# motiondetector.net
KiCad netlist of a schematic drawn in EAGLE
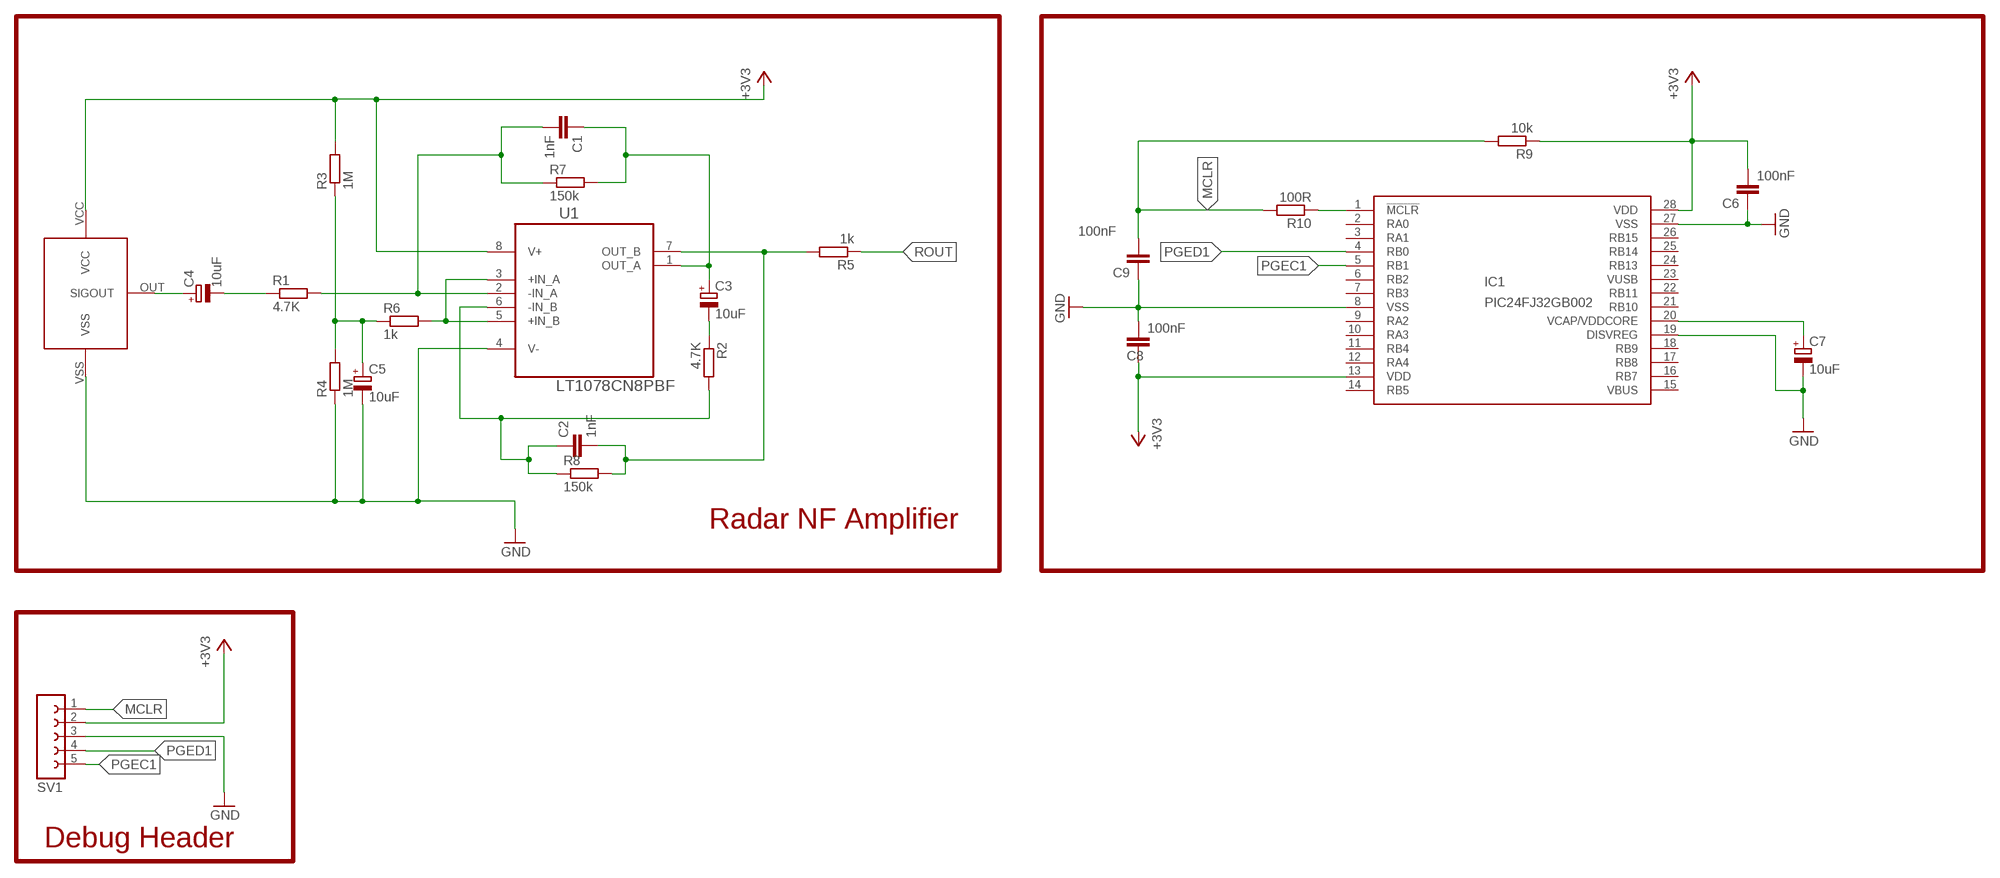
[diagram p0: schematic, sheet 1]

(export (version "E")
  (design (tool "Eeschema 10.0.6"))
  (components
    (comp (ref "C1")
      (value "1nF")
      (footprint "eagle-import:C025-025X050")
      (libsource (lib "eagle-import") (part "C-EU025-025X050"))
    )
    (comp (ref "C2")
      (value "1nF")
      (footprint "eagle-import:C025-025X050")
      (libsource (lib "eagle-import") (part "C-EU025-025X050"))
    )
    (comp (ref "C3")
      (value "10uF")
      (footprint "eagle-import:E2,5-5")
      (libsource (lib "eagle-import") (part "CPOL-EUE2.5-5"))
    )
    (comp (ref "C4")
      (value "10uF")
      (footprint "eagle-import:E2,5-5")
      (libsource (lib "eagle-import") (part "CPOL-EUE2.5-5"))
    )
    (comp (ref "C5")
      (value "10uF")
      (footprint "eagle-import:E2,5-5")
      (libsource (lib "eagle-import") (part "CPOL-EUE2.5-5"))
    )
    (comp (ref "C6")
      (value "100nF")
      (footprint "eagle-import:C025-025X050")
      (libsource (lib "eagle-import") (part "C-EU025-025X050"))
    )
    (comp (ref "C7")
      (value "10uF")
      (footprint "eagle-import:E2,5-5")
      (libsource (lib "eagle-import") (part "CPOL-EUE2.5-5"))
    )
    (comp (ref "C8")
      (value "100nF")
      (footprint "eagle-import:C025-025X050")
      (libsource (lib "eagle-import") (part "C-EU025-025X050"))
    )
    (comp (ref "C9")
      (value "100nF")
      (footprint "eagle-import:C025-025X050")
      (libsource (lib "eagle-import") (part "C-EU025-025X050"))
    )
    (comp (ref "IC1")
      (value "PIC24FJ32GB002")
      (footprint "eagle-import:DIL28-3")
      (libsource (lib "eagle-import") (part "PIC24FJ32GB002"))
    )
    (comp (ref "R1")
      (value "4.7K")
      (footprint "eagle-import:0207_10")
      (libsource (lib "eagle-import") (part "R-EU_0207/10"))
    )
    (comp (ref "R2")
      (value "4.7K")
      (footprint "eagle-import:0207_10")
      (libsource (lib "eagle-import") (part "R-EU_0207/10"))
    )
    (comp (ref "R3")
      (value "1M")
      (footprint "eagle-import:0207_10")
      (libsource (lib "eagle-import") (part "R-EU_0207/10"))
    )
    (comp (ref "R4")
      (value "1M")
      (footprint "eagle-import:0207_10")
      (libsource (lib "eagle-import") (part "R-EU_0207/10"))
    )
    (comp (ref "R5")
      (value "1k")
      (footprint "eagle-import:0207_10")
      (libsource (lib "eagle-import") (part "R-EU_0207/10"))
    )
    (comp (ref "R6")
      (value "1k")
      (footprint "eagle-import:0207_10")
      (libsource (lib "eagle-import") (part "R-EU_0207/10"))
    )
    (comp (ref "R7")
      (value "150k")
      (footprint "eagle-import:0207_10")
      (libsource (lib "eagle-import") (part "R-EU_0207/10"))
    )
    (comp (ref "R8")
      (value "150k")
      (footprint "eagle-import:0207_10")
      (libsource (lib "eagle-import") (part "R-EU_0207/10"))
    )
    (comp (ref "R9")
      (value "10k")
      (footprint "eagle-import:0207_10")
      (libsource (lib "eagle-import") (part "R-EU_0207/10"))
    )
    (comp (ref "R10")
      (value "100R")
      (footprint "eagle-import:0207_10")
      (libsource (lib "eagle-import") (part "R-EU_0207/10"))
    )
    (comp (ref "SV1")
      (value "FE05-1")
      (footprint "eagle-import:FE05-1")
      (libsource (lib "eagle-import") (part "FE05-1"))
    )
    (comp (ref "U$1")
      (value "RSM3650")
      (footprint "eagle-import:RSM3650")
      (libsource (lib "eagle-import") (part "RSM3650"))
    )
    (comp (ref "U1")
      (value "LT1078CN8PBF")
      (footprint "eagle-import:DIP254P762X393-8")
      (fields (field (name "MPN") "LT1078CN8#PBF"))
      (libsource (lib "eagle-import") (part "LT1078CN8PBF"))
    )
  )
  (nets
    (net (code "1") (name "+3V3") (class "Default")
      (node (ref "C6") (pin "2") (pinfunction "2_2") (pintype "passive"))
      (node (ref "C8") (pin "1") (pinfunction "1_1") (pintype "passive"))
      (node (ref "IC1") (pin "13") (pinfunction "VDD_13") (pintype "power_in"))
      (node (ref "IC1") (pin "28") (pinfunction "VDD_28") (pintype "power_in"))
      (node (ref "R3") (pin "2") (pinfunction "2_2") (pintype "passive"))
      (node (ref "R9") (pin "1") (pinfunction "1_1") (pintype "passive"))
      (node (ref "SV1") (pin "2") (pinfunction "2_2") (pintype "passive"))
      (node (ref "U$1") (pin "VCC") (pinfunction "VCC_VCC") (pintype "power_in"))
      (node (ref "U1") (pin "8") (pinfunction "V+_8") (pintype "power_in"))
    )
    (net (code "2") (name "GND") (class "Default")
      (node (ref "C5") (pin "-") (pinfunction "-_-") (pintype "passive"))
      (node (ref "C6") (pin "1") (pinfunction "1_1") (pintype "passive"))
      (node (ref "C7") (pin "-") (pinfunction "-_-") (pintype "passive"))
      (node (ref "C8") (pin "2") (pinfunction "2_2") (pintype "passive"))
      (node (ref "C9") (pin "1") (pinfunction "1_1") (pintype "passive"))
      (node (ref "IC1") (pin "19") (pinfunction "DISVREG_19") (pintype "passive"))
      (node (ref "IC1") (pin "27") (pinfunction "VSS_27") (pintype "power_in"))
      (node (ref "IC1") (pin "8") (pinfunction "VSS_8") (pintype "power_in"))
      (node (ref "R4") (pin "1") (pinfunction "1_1") (pintype "passive"))
      (node (ref "SV1") (pin "3") (pinfunction "3_3") (pintype "passive"))
      (node (ref "U$1") (pin "VSS") (pinfunction "VSS_VSS") (pintype "power_in"))
      (node (ref "U1") (pin "4") (pinfunction "V-_4") (pintype "power_in"))
    )
    (net (code "3") (name "MCLR") (class "Default")
      (node (ref "C9") (pin "2") (pinfunction "2_2") (pintype "passive"))
      (node (ref "R10") (pin "2") (pinfunction "2_2") (pintype "passive"))
      (node (ref "R9") (pin "2") (pinfunction "2_2") (pintype "passive"))
      (node (ref "SV1") (pin "1") (pinfunction "1_1") (pintype "passive"))
    )
    (net (code "4") (name "Net-(C3-Pad-)") (class "Default")
      (node (ref "C3") (pin "-") (pinfunction "-_-") (pintype "passive"))
      (node (ref "R2") (pin "1") (pinfunction "1_1") (pintype "passive"))
    )
    (net (code "5") (name "Net-(C4-Pad-)") (class "Default")
      (node (ref "C4") (pin "-") (pinfunction "-_-") (pintype "passive"))
      (node (ref "R1") (pin "1") (pinfunction "1_1") (pintype "passive"))
    )
    (net (code "6") (name "Net-(C5-Pad+)") (class "Default")
      (node (ref "C5") (pin "+") (pinfunction "+_+") (pintype "passive"))
      (node (ref "R3") (pin "1") (pinfunction "1_1") (pintype "passive"))
      (node (ref "R4") (pin "2") (pinfunction "2_2") (pintype "passive"))
      (node (ref "R6") (pin "1") (pinfunction "1_1") (pintype "passive"))
    )
    (net (code "7") (name "Net-(IC1-VCAP{slash}VDDCORE)") (class "Default")
      (node (ref "C7") (pin "+") (pinfunction "+_+") (pintype "passive"))
      (node (ref "IC1") (pin "20") (pinfunction "VCAP/VDDCORE_20") (pintype "power_in"))
    )
    (net (code "8") (name "Net-(IC1-~{MCLR})") (class "Default")
      (node (ref "IC1") (pin "1") (pinfunction "~{MCLR}_1") (pintype "bidirectional"))
      (node (ref "R10") (pin "1") (pinfunction "1_1") (pintype "passive"))
    )
    (net (code "9") (name "Net-(U$1-SIGOUT)") (class "Default")
      (node (ref "C4") (pin "+") (pinfunction "+_+") (pintype "passive"))
      (node (ref "U$1") (pin "OUT") (pinfunction "SIGOUT_OUT") (pintype "output"))
    )
    (net (code "10") (name "Net-(U1-+IN_A)") (class "Default")
      (node (ref "R6") (pin "2") (pinfunction "2_2") (pintype "passive"))
      (node (ref "U1") (pin "3") (pinfunction "+IN_A_3") (pintype "input"))
      (node (ref "U1") (pin "5") (pinfunction "+IN_B_5") (pintype "input"))
    )
    (net (code "11") (name "Net-(U1--IN_A)") (class "Default")
      (node (ref "C1") (pin "2") (pinfunction "2_2") (pintype "passive"))
      (node (ref "R1") (pin "2") (pinfunction "2_2") (pintype "passive"))
      (node (ref "R7") (pin "1") (pinfunction "1_1") (pintype "passive"))
      (node (ref "U1") (pin "2") (pinfunction "-IN_A_2") (pintype "input"))
    )
    (net (code "12") (name "Net-(U1--IN_B)") (class "Default")
      (node (ref "C2") (pin "1") (pinfunction "1_1") (pintype "passive"))
      (node (ref "R2") (pin "2") (pinfunction "2_2") (pintype "passive"))
      (node (ref "R8") (pin "1") (pinfunction "1_1") (pintype "passive"))
      (node (ref "U1") (pin "6") (pinfunction "-IN_B_6") (pintype "input"))
    )
    (net (code "13") (name "Net-(U1-OUT_A)") (class "Default")
      (node (ref "C1") (pin "1") (pinfunction "1_1") (pintype "passive"))
      (node (ref "C3") (pin "+") (pinfunction "+_+") (pintype "passive"))
      (node (ref "R7") (pin "2") (pinfunction "2_2") (pintype "passive"))
      (node (ref "U1") (pin "1") (pinfunction "OUT_A_1") (pintype "output"))
    )
    (net (code "14") (name "Net-(U1-OUT_B)") (class "Default")
      (node (ref "C2") (pin "2") (pinfunction "2_2") (pintype "passive"))
      (node (ref "R5") (pin "2") (pinfunction "2_2") (pintype "passive"))
      (node (ref "R8") (pin "2") (pinfunction "2_2") (pintype "passive"))
      (node (ref "U1") (pin "7") (pinfunction "OUT_B_7") (pintype "output"))
    )
    (net (code "15") (name "PGEC1") (class "Default")
      (node (ref "IC1") (pin "5") (pinfunction "RB1_5") (pintype "bidirectional"))
      (node (ref "SV1") (pin "5") (pinfunction "5_5") (pintype "passive"))
    )
    (net (code "16") (name "PGED1") (class "Default")
      (node (ref "IC1") (pin "4") (pinfunction "RB0_4") (pintype "bidirectional"))
      (node (ref "SV1") (pin "4") (pinfunction "4_4") (pintype "passive"))
    )
    (net (code "17") (name "ROUT") (class "Default")
      (node (ref "R5") (pin "1") (pinfunction "1_1") (pintype "passive"))
    )
    (net (code "18") (name "unconnected-(IC1-RA0-Pad2)") (class "Default")
      (node (ref "IC1") (pin "2") (pinfunction "RA0_2") (pintype "bidirectional"))
    )
    (net (code "19") (name "unconnected-(IC1-RA1-Pad3)") (class "Default")
      (node (ref "IC1") (pin "3") (pinfunction "RA1_3") (pintype "bidirectional"))
    )
    (net (code "20") (name "unconnected-(IC1-RA2-Pad9)") (class "Default")
      (node (ref "IC1") (pin "9") (pinfunction "RA2_9") (pintype "bidirectional"))
    )
    (net (code "21") (name "unconnected-(IC1-RA3-Pad10)") (class "Default")
      (node (ref "IC1") (pin "10") (pinfunction "RA3_10") (pintype "bidirectional"))
    )
    (net (code "22") (name "unconnected-(IC1-RA4-Pad12)") (class "Default")
      (node (ref "IC1") (pin "12") (pinfunction "RA4_12") (pintype "bidirectional"))
    )
    (net (code "23") (name "unconnected-(IC1-RB2-Pad6)") (class "Default")
      (node (ref "IC1") (pin "6") (pinfunction "RB2_6") (pintype "bidirectional"))
    )
    (net (code "24") (name "unconnected-(IC1-RB3-Pad7)") (class "Default")
      (node (ref "IC1") (pin "7") (pinfunction "RB3_7") (pintype "bidirectional"))
    )
    (net (code "25") (name "unconnected-(IC1-RB4-Pad11)") (class "Default")
      (node (ref "IC1") (pin "11") (pinfunction "RB4_11") (pintype "bidirectional"))
    )
    (net (code "26") (name "unconnected-(IC1-RB5-Pad14)") (class "Default")
      (node (ref "IC1") (pin "14") (pinfunction "RB5_14") (pintype "bidirectional"))
    )
    (net (code "27") (name "unconnected-(IC1-RB7-Pad16)") (class "Default")
      (node (ref "IC1") (pin "16") (pinfunction "RB7_16") (pintype "bidirectional"))
    )
    (net (code "28") (name "unconnected-(IC1-RB8-Pad17)") (class "Default")
      (node (ref "IC1") (pin "17") (pinfunction "RB8_17") (pintype "input"))
    )
    (net (code "29") (name "unconnected-(IC1-RB9-Pad18)") (class "Default")
      (node (ref "IC1") (pin "18") (pinfunction "RB9_18") (pintype "output"))
    )
    (net (code "30") (name "unconnected-(IC1-RB10-Pad21)") (class "Default")
      (node (ref "IC1") (pin "21") (pinfunction "RB10_21") (pintype "input"))
    )
    (net (code "31") (name "unconnected-(IC1-RB11-Pad22)") (class "Default")
      (node (ref "IC1") (pin "22") (pinfunction "RB11_22") (pintype "input"))
    )
    (net (code "32") (name "unconnected-(IC1-RB13-Pad24)") (class "Default")
      (node (ref "IC1") (pin "24") (pinfunction "RB13_24") (pintype "bidirectional"))
    )
    (net (code "33") (name "unconnected-(IC1-RB14-Pad25)") (class "Default")
      (node (ref "IC1") (pin "25") (pinfunction "RB14_25") (pintype "bidirectional"))
    )
    (net (code "34") (name "unconnected-(IC1-RB15-Pad26)") (class "Default")
      (node (ref "IC1") (pin "26") (pinfunction "RB15_26") (pintype "bidirectional"))
    )
    (net (code "35") (name "unconnected-(IC1-VBUS-Pad15)") (class "Default")
      (node (ref "IC1") (pin "15") (pinfunction "VBUS_15") (pintype "bidirectional"))
    )
    (net (code "36") (name "unconnected-(IC1-VUSB-Pad23)") (class "Default")
      (node (ref "IC1") (pin "23") (pinfunction "VUSB_23") (pintype "bidirectional"))
    )
  )
)
